# Luxeon_Rebel_Controller_Board.net
KiCad netlist of a schematic drawn in EAGLE
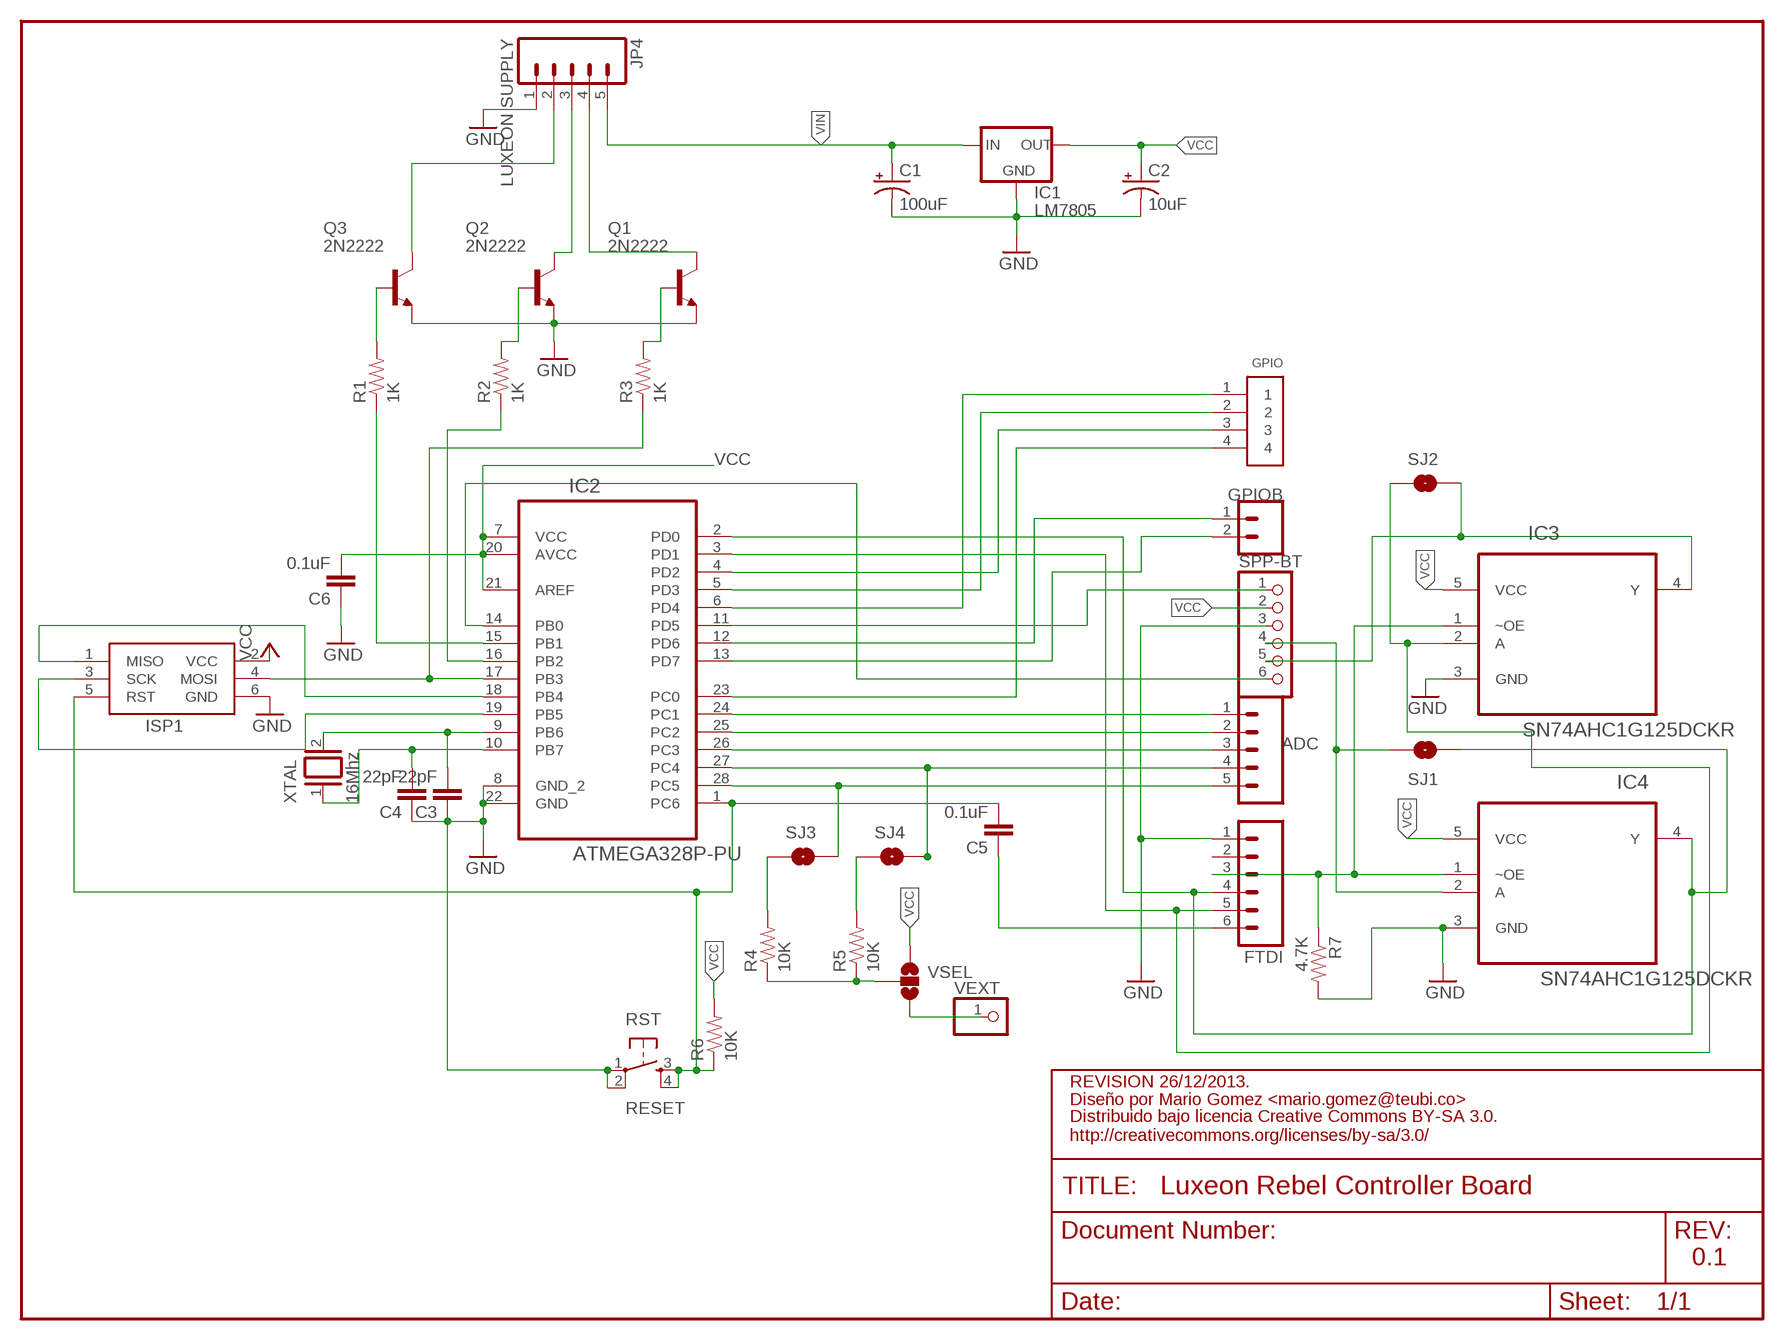
[diagram p0: schematic, sheet 1]

(export (version "E")
  (design (tool "Eeschema 10.0.6"))
  (components
    (comp (ref "ADC")
      (value "M05PTH")
      (footprint "eagle-import:1X05")
      (libsource (lib "eagle-import") (part "SparkFun-Connectors_M05PTH"))
    )
    (comp (ref "C1")
      (value "100uF")
      (footprint "eagle-import:CPOL-RADIAL-100UF-25V")
      (libsource (lib "eagle-import") (part "CAP_POLPTH1"))
    )
    (comp (ref "C2")
      (value "10uF")
      (footprint "eagle-import:CPOL-RADIAL-10UF-25V")
      (libsource (lib "eagle-import") (part "CAP_POLPTH2"))
    )
    (comp (ref "C3")
      (value "22pF")
      (footprint "eagle-import:CAP-PTH-SMALL")
      (libsource (lib "eagle-import") (part "CAPPTH"))
    )
    (comp (ref "C4")
      (value "22pF")
      (footprint "eagle-import:CAP-PTH-SMALL")
      (libsource (lib "eagle-import") (part "CAPPTH"))
    )
    (comp (ref "C5")
      (value "0.1uF")
      (footprint "eagle-import:CAP-PTH-SMALL")
      (libsource (lib "eagle-import") (part "CAPPTH"))
    )
    (comp (ref "C6")
      (value "0.1uF")
      (footprint "eagle-import:CAP-PTH-SMALL")
      (libsource (lib "eagle-import") (part "CAPPTH"))
    )
    (comp (ref "FTDI")
      (value "M06SIP")
      (footprint "eagle-import:1X06")
      (libsource (lib "eagle-import") (part "M06SIP"))
    )
    (comp (ref "GPIO")
      (value "1X4-BIG")
      (footprint "eagle-import:1X04-BIG")
      (libsource (lib "eagle-import") (part "1X4-BIG"))
    )
    (comp (ref "GPIOB")
      (value "M02PTH")
      (footprint "eagle-import:1X02")
      (libsource (lib "eagle-import") (part "M02PTH"))
    )
    (comp (ref "IC1")
      (value "LM7805")
      (footprint "eagle-import:78XXL")
      (libsource (lib "eagle-import") (part "V_REG_78XXSIDE"))
    )
    (comp (ref "IC2")
      (value "ATMEGA328P-PU")
      (footprint "eagle-import:DIP254P762X457-28")
      (libsource (lib "eagle-import") (part "ATMEGA328P-PU"))
    )
    (comp (ref "IC3")
      (value "SN74AHC1G125DCKR")
      (footprint "eagle-import:SOT65P210X110-5N")
      (libsource (lib "eagle-import") (part "SN74AHC1G125DCKR"))
    )
    (comp (ref "IC4")
      (value "SN74AHC1G125DCKR")
      (footprint "eagle-import:SOT65P210X110-5N")
      (libsource (lib "eagle-import") (part "SN74AHC1G125DCKR"))
    )
    (comp (ref "ISP1")
      (value "AVRISP-6")
      (footprint "eagle-import:AVRISP")
      (libsource (lib "eagle-import") (part "AVRISP-6"))
    )
    (comp (ref "JP4")
      (value "LUXEON SUPPLY")
      (footprint "eagle-import:1X05_LONGPADS")
      (libsource (lib "eagle-import") (part "M05PTH_LONGPADS"))
    )
    (comp (ref "Q1")
      (value "2N2222")
      (footprint "eagle-import:TO92-EBC-OVAL")
      (libsource (lib "eagle-import") (part "2N2222"))
    )
    (comp (ref "Q2")
      (value "2N2222")
      (footprint "eagle-import:TO92-EBC-OVAL")
      (libsource (lib "eagle-import") (part "2N2222"))
    )
    (comp (ref "Q3")
      (value "2N2222")
      (footprint "eagle-import:TO92-EBC-OVAL")
      (libsource (lib "eagle-import") (part "2N2222"))
    )
    (comp (ref "R1")
      (value "1K")
      (footprint "eagle-import:AXIAL-0.3")
      (libsource (lib "eagle-import") (part "RESISTORAXIAL-0.3"))
    )
    (comp (ref "R2")
      (value "1K")
      (footprint "eagle-import:AXIAL-0.3")
      (libsource (lib "eagle-import") (part "RESISTORAXIAL-0.3"))
    )
    (comp (ref "R3")
      (value "1K")
      (footprint "eagle-import:AXIAL-0.3")
      (libsource (lib "eagle-import") (part "RESISTORAXIAL-0.3"))
    )
    (comp (ref "R4")
      (value "10K")
      (footprint "eagle-import:AXIAL-0.3")
      (libsource (lib "eagle-import") (part "RESISTORAXIAL-0.3"))
    )
    (comp (ref "R5")
      (value "10K")
      (footprint "eagle-import:AXIAL-0.3")
      (libsource (lib "eagle-import") (part "RESISTORAXIAL-0.3"))
    )
    (comp (ref "R6")
      (value "10K")
      (footprint "eagle-import:AXIAL-0.3")
      (libsource (lib "eagle-import") (part "RESISTORAXIAL-0.3"))
    )
    (comp (ref "R7")
      (value "4.7K")
      (footprint "eagle-import:0603-RES")
      (libsource (lib "eagle-import") (part "RESISTOR0603-RES"))
    )
    (comp (ref "RST")
      (value "RESET")
      (footprint "eagle-import:TACTILE-PTH")
      (libsource (lib "eagle-import") (part "TAC_SWITCHPTH"))
    )
    (comp (ref "SJ1")
      (value "SOLDERJUMPERNC")
      (footprint "eagle-import:SJ_2S")
      (libsource (lib "eagle-import") (part "SOLDERJUMPERNC"))
    )
    (comp (ref "SJ2")
      (value "SOLDERJUMPERNC")
      (footprint "eagle-import:SJ_2S")
      (libsource (lib "eagle-import") (part "SOLDERJUMPERNC"))
    )
    (comp (ref "SJ3")
      (value "SOLDERJUMPERTRACE")
      (footprint "eagle-import:SJ_2S-TRACE")
      (libsource (lib "eagle-import") (part "SOLDERJUMPERTRACE"))
    )
    (comp (ref "SJ4")
      (value "SOLDERJUMPERTRACE")
      (footprint "eagle-import:SJ_2S-TRACE")
      (libsource (lib "eagle-import") (part "SOLDERJUMPERTRACE"))
    )
    (comp (ref "SPP-BT")
      (value "PINHD-1X6")
      (footprint "eagle-import:1X06")
      (libsource (lib "eagle-import") (part "PINHD-1X6"))
    )
    (comp (ref "VEXT")
      (value "PINHD-1X1")
      (footprint "eagle-import:1X01")
      (libsource (lib "eagle-import") (part "PINHD-1X1"))
    )
    (comp (ref "VSEL")
      (value "SOLDERJUMPER_2WAY-OLDS")
      (footprint "eagle-import:SJ_3")
      (libsource (lib "eagle-import") (part "SOLDERJUMPER_2WAY-OLDS"))
    )
    (comp (ref "XTAL")
      (value "16Mhz")
      (footprint "eagle-import:QS")
      (libsource (lib "eagle-import") (part "XTAL/S"))
    )
  )
  (nets
    (net (code "1") (name "GND") (class "Default")
      (node (ref "C1") (pin "2") (pinfunction "-_2") (pintype "passive"))
      (node (ref "C2") (pin "2") (pinfunction "-_2") (pintype "passive"))
      (node (ref "C3") (pin "1") (pinfunction "1_1") (pintype "passive"))
      (node (ref "C4") (pin "1") (pinfunction "1_1") (pintype "passive"))
      (node (ref "C6") (pin "1") (pinfunction "1_1") (pintype "passive"))
      (node (ref "FTDI") (pin "1") (pinfunction "1_1") (pintype "passive"))
      (node (ref "IC1") (pin "GND") (pinfunction "GND_GND") (pintype "input"))
      (node (ref "IC2") (pin "22") (pinfunction "GND_22") (pintype "passive"))
      (node (ref "IC2") (pin "8") (pinfunction "GND_2_8") (pintype "passive"))
      (node (ref "IC3") (pin "3") (pinfunction "GND_3") (pintype "passive"))
      (node (ref "IC4") (pin "3") (pinfunction "GND_3") (pintype "passive"))
      (node (ref "ISP1") (pin "6") (pinfunction "GND_6") (pintype "power_in"))
      (node (ref "JP4") (pin "1") (pinfunction "1_1") (pintype "passive"))
      (node (ref "Q1") (pin "E") (pinfunction "E_E") (pintype "passive"))
      (node (ref "Q2") (pin "E") (pinfunction "E_E") (pintype "passive"))
      (node (ref "Q3") (pin "E") (pinfunction "E_E") (pintype "passive"))
      (node (ref "R7") (pin "2") (pinfunction "2_2") (pintype "passive"))
      (node (ref "RST") (pin "1") (pinfunction "1_1") (pintype "passive"))
      (node (ref "RST") (pin "2") (pinfunction "2_2") (pintype "passive"))
      (node (ref "SPP-BT") (pin "3") (pinfunction "3_3") (pintype "passive"))
    )
    (net (code "2") (name "Net-(C5-Pad1)") (class "Default")
      (node (ref "C5") (pin "1") (pinfunction "1_1") (pintype "passive"))
      (node (ref "FTDI") (pin "6") (pinfunction "6_6") (pintype "passive"))
    )
    (net (code "3") (name "Net-(IC2-PB0)") (class "Default")
      (node (ref "IC2") (pin "14") (pinfunction "PB0_14") (pintype "bidirectional"))
      (node (ref "SPP-BT") (pin "6") (pinfunction "6_6") (pintype "passive"))
    )
    (net (code "4") (name "Net-(IC2-PB1)") (class "Default")
      (node (ref "IC2") (pin "15") (pinfunction "PB1_15") (pintype "bidirectional"))
      (node (ref "R1") (pin "P$1") (pinfunction "1_P$1") (pintype "passive"))
    )
    (net (code "5") (name "Net-(IC2-PB2)") (class "Default")
      (node (ref "IC2") (pin "16") (pinfunction "PB2_16") (pintype "bidirectional"))
      (node (ref "R2") (pin "P$1") (pinfunction "1_P$1") (pintype "passive"))
    )
    (net (code "6") (name "Net-(IC2-PB3)") (class "Default")
      (node (ref "IC2") (pin "17") (pinfunction "PB3_17") (pintype "bidirectional"))
      (node (ref "ISP1") (pin "4") (pinfunction "MOSI_4") (pintype "output"))
      (node (ref "R3") (pin "P$1") (pinfunction "1_P$1") (pintype "passive"))
    )
    (net (code "7") (name "Net-(IC2-PB4)") (class "Default")
      (node (ref "IC2") (pin "18") (pinfunction "PB4_18") (pintype "bidirectional"))
      (node (ref "ISP1") (pin "1") (pinfunction "MISO_1") (pintype "input"))
    )
    (net (code "8") (name "Net-(IC2-PB5)") (class "Default")
      (node (ref "IC2") (pin "19") (pinfunction "PB5_19") (pintype "bidirectional"))
      (node (ref "ISP1") (pin "3") (pinfunction "SCK_3") (pintype "output"))
    )
    (net (code "9") (name "Net-(IC2-PB6)") (class "Default")
      (node (ref "C3") (pin "2") (pinfunction "2_2") (pintype "passive"))
      (node (ref "IC2") (pin "9") (pinfunction "PB6_9") (pintype "bidirectional"))
      (node (ref "XTAL") (pin "2") (pinfunction "2_2") (pintype "passive"))
    )
    (net (code "10") (name "Net-(IC2-PB7)") (class "Default")
      (node (ref "C4") (pin "2") (pinfunction "2_2") (pintype "passive"))
      (node (ref "IC2") (pin "10") (pinfunction "PB7_10") (pintype "bidirectional"))
      (node (ref "XTAL") (pin "1") (pinfunction "1_1") (pintype "passive"))
    )
    (net (code "11") (name "Net-(IC2-PC0)") (class "Default")
      (node (ref "GPIO") (pin "4") (pinfunction "4_4") (pintype "bidirectional"))
      (node (ref "IC2") (pin "23") (pinfunction "PC0_23") (pintype "bidirectional"))
    )
    (net (code "12") (name "Net-(IC2-PC1)") (class "Default")
      (node (ref "ADC") (pin "1") (pinfunction "1_1") (pintype "passive"))
      (node (ref "IC2") (pin "24") (pinfunction "PC1_24") (pintype "bidirectional"))
    )
    (net (code "13") (name "Net-(IC2-PC2)") (class "Default")
      (node (ref "ADC") (pin "2") (pinfunction "2_2") (pintype "passive"))
      (node (ref "IC2") (pin "25") (pinfunction "PC2_25") (pintype "bidirectional"))
    )
    (net (code "14") (name "Net-(IC2-PC3)") (class "Default")
      (node (ref "ADC") (pin "3") (pinfunction "3_3") (pintype "passive"))
      (node (ref "IC2") (pin "26") (pinfunction "PC3_26") (pintype "bidirectional"))
    )
    (net (code "15") (name "Net-(IC2-PC4)") (class "Default")
      (node (ref "ADC") (pin "4") (pinfunction "4_4") (pintype "passive"))
      (node (ref "IC2") (pin "27") (pinfunction "PC4_27") (pintype "bidirectional"))
      (node (ref "SJ4") (pin "2") (pinfunction "2_2") (pintype "passive"))
    )
    (net (code "16") (name "Net-(IC2-PC5)") (class "Default")
      (node (ref "ADC") (pin "5") (pinfunction "5_5") (pintype "passive"))
      (node (ref "IC2") (pin "28") (pinfunction "PC5_28") (pintype "bidirectional"))
      (node (ref "SJ3") (pin "2") (pinfunction "2_2") (pintype "passive"))
    )
    (net (code "17") (name "Net-(IC2-PC6)") (class "Default")
      (node (ref "C5") (pin "2") (pinfunction "2_2") (pintype "passive"))
      (node (ref "IC2") (pin "1") (pinfunction "PC6_1") (pintype "bidirectional"))
      (node (ref "ISP1") (pin "5") (pinfunction "RST_5") (pintype "output"))
      (node (ref "R6") (pin "P$1") (pinfunction "1_P$1") (pintype "passive"))
      (node (ref "RST") (pin "3") (pinfunction "3_3") (pintype "passive"))
      (node (ref "RST") (pin "4") (pinfunction "4_4") (pintype "passive"))
    )
    (net (code "18") (name "Net-(IC2-PD0)") (class "Default")
      (node (ref "FTDI") (pin "4") (pinfunction "4_4") (pintype "passive"))
      (node (ref "IC2") (pin "2") (pinfunction "PD0_2") (pintype "bidirectional"))
      (node (ref "IC4") (pin "4") (pinfunction "Y_4") (pintype "output"))
      (node (ref "SJ1") (pin "2") (pinfunction "2_2") (pintype "passive"))
    )
    (net (code "19") (name "Net-(IC2-PD1)") (class "Default")
      (node (ref "FTDI") (pin "5") (pinfunction "5_5") (pintype "passive"))
      (node (ref "IC2") (pin "3") (pinfunction "PD1_3") (pintype "bidirectional"))
      (node (ref "IC3") (pin "2") (pinfunction "A_2") (pintype "input"))
      (node (ref "SJ2") (pin "1") (pinfunction "1_1") (pintype "passive"))
    )
    (net (code "20") (name "Net-(IC2-PD2)") (class "Default")
      (node (ref "GPIO") (pin "3") (pinfunction "3_3") (pintype "bidirectional"))
      (node (ref "IC2") (pin "4") (pinfunction "PD2_4") (pintype "bidirectional"))
    )
    (net (code "21") (name "Net-(IC2-PD3)") (class "Default")
      (node (ref "GPIO") (pin "2") (pinfunction "2_2") (pintype "bidirectional"))
      (node (ref "IC2") (pin "5") (pinfunction "PD3_5") (pintype "bidirectional"))
    )
    (net (code "22") (name "Net-(IC2-PD4)") (class "Default")
      (node (ref "GPIO") (pin "1") (pinfunction "1_1") (pintype "bidirectional"))
      (node (ref "IC2") (pin "6") (pinfunction "PD4_6") (pintype "bidirectional"))
    )
    (net (code "23") (name "Net-(IC2-PD5)") (class "Default")
      (node (ref "IC2") (pin "11") (pinfunction "PD5_11") (pintype "bidirectional"))
      (node (ref "SPP-BT") (pin "1") (pinfunction "1_1") (pintype "passive"))
    )
    (net (code "24") (name "Net-(IC2-PD6)") (class "Default")
      (node (ref "GPIOB") (pin "1") (pinfunction "1_1") (pintype "passive"))
      (node (ref "IC2") (pin "12") (pinfunction "PD6_12") (pintype "bidirectional"))
    )
    (net (code "25") (name "Net-(IC2-PD7)") (class "Default")
      (node (ref "GPIOB") (pin "2") (pinfunction "2_2") (pintype "passive"))
      (node (ref "IC2") (pin "13") (pinfunction "PD7_13") (pintype "bidirectional"))
    )
    (net (code "26") (name "Net-(IC3-Y)") (class "Default")
      (node (ref "IC3") (pin "4") (pinfunction "Y_4") (pintype "output"))
      (node (ref "SJ2") (pin "2") (pinfunction "2_2") (pintype "passive"))
      (node (ref "SPP-BT") (pin "5") (pinfunction "5_5") (pintype "passive"))
    )
    (net (code "27") (name "Net-(IC3-~{OE})") (class "Default")
      (node (ref "FTDI") (pin "3") (pinfunction "3_3") (pintype "passive"))
      (node (ref "IC3") (pin "1") (pinfunction "~{OE}_1") (pintype "input"))
      (node (ref "IC4") (pin "1") (pinfunction "~{OE}_1") (pintype "input"))
      (node (ref "R7") (pin "1") (pinfunction "1_1") (pintype "passive"))
    )
    (net (code "28") (name "Net-(IC4-A)") (class "Default")
      (node (ref "IC4") (pin "2") (pinfunction "A_2") (pintype "input"))
      (node (ref "SJ1") (pin "1") (pinfunction "1_1") (pintype "passive"))
      (node (ref "SPP-BT") (pin "4") (pinfunction "4_4") (pintype "passive"))
    )
    (net (code "29") (name "Net-(JP4-Pad2)") (class "Default")
      (node (ref "JP4") (pin "2") (pinfunction "2_2") (pintype "passive"))
      (node (ref "Q3") (pin "C") (pinfunction "C_C") (pintype "passive"))
    )
    (net (code "30") (name "Net-(JP4-Pad3)") (class "Default")
      (node (ref "JP4") (pin "3") (pinfunction "3_3") (pintype "passive"))
      (node (ref "Q2") (pin "C") (pinfunction "C_C") (pintype "passive"))
    )
    (net (code "31") (name "Net-(JP4-Pad4)") (class "Default")
      (node (ref "JP4") (pin "4") (pinfunction "4_4") (pintype "passive"))
      (node (ref "Q1") (pin "C") (pinfunction "C_C") (pintype "passive"))
    )
    (net (code "32") (name "Net-(R1-2)") (class "Default")
      (node (ref "Q3") (pin "B") (pinfunction "B_B") (pintype "passive"))
      (node (ref "R1") (pin "P$2") (pinfunction "2_P$2") (pintype "passive"))
    )
    (net (code "33") (name "Net-(R2-2)") (class "Default")
      (node (ref "Q2") (pin "B") (pinfunction "B_B") (pintype "passive"))
      (node (ref "R2") (pin "P$2") (pinfunction "2_P$2") (pintype "passive"))
    )
    (net (code "34") (name "Net-(R3-2)") (class "Default")
      (node (ref "Q1") (pin "B") (pinfunction "B_B") (pintype "passive"))
      (node (ref "R3") (pin "P$2") (pinfunction "2_P$2") (pintype "passive"))
    )
    (net (code "35") (name "Net-(R4-1)") (class "Default")
      (node (ref "R4") (pin "P$1") (pinfunction "1_P$1") (pintype "passive"))
      (node (ref "R5") (pin "P$1") (pinfunction "1_P$1") (pintype "passive"))
      (node (ref "VSEL") (pin "2") (pinfunction "2_2") (pintype "passive"))
    )
    (net (code "36") (name "Net-(R4-2)") (class "Default")
      (node (ref "R4") (pin "P$2") (pinfunction "2_P$2") (pintype "passive"))
      (node (ref "SJ3") (pin "1") (pinfunction "1_1") (pintype "passive"))
    )
    (net (code "37") (name "Net-(R5-2)") (class "Default")
      (node (ref "R5") (pin "P$2") (pinfunction "2_P$2") (pintype "passive"))
      (node (ref "SJ4") (pin "1") (pinfunction "1_1") (pintype "passive"))
    )
    (net (code "38") (name "Net-(VEXT-Pad1)") (class "Default")
      (node (ref "VEXT") (pin "1") (pinfunction "1_1") (pintype "passive"))
      (node (ref "VSEL") (pin "3") (pinfunction "3_3") (pintype "passive"))
    )
    (net (code "39") (name "VCC") (class "Default")
      (node (ref "C2") (pin "1") (pinfunction "+_1") (pintype "passive"))
      (node (ref "C6") (pin "2") (pinfunction "2_2") (pintype "passive"))
      (node (ref "IC1") (pin "OUT") (pinfunction "OUT_OUT") (pintype "output"))
      (node (ref "IC2") (pin "20") (pinfunction "AVCC_20") (pintype "power_in"))
      (node (ref "IC2") (pin "21") (pinfunction "AREF_21") (pintype "input"))
      (node (ref "IC2") (pin "7") (pinfunction "VCC_7") (pintype "power_in"))
      (node (ref "IC3") (pin "5") (pinfunction "VCC_5") (pintype "power_in"))
      (node (ref "IC4") (pin "5") (pinfunction "VCC_5") (pintype "power_in"))
      (node (ref "ISP1") (pin "2") (pinfunction "VCC_2") (pintype "power_in"))
      (node (ref "R6") (pin "P$2") (pinfunction "2_P$2") (pintype "passive"))
      (node (ref "SPP-BT") (pin "2") (pinfunction "2_2") (pintype "passive"))
      (node (ref "VSEL") (pin "1") (pinfunction "1_1") (pintype "passive"))
    )
    (net (code "40") (name "VIN") (class "Default")
      (node (ref "C1") (pin "1") (pinfunction "+_1") (pintype "passive"))
      (node (ref "IC1") (pin "IN") (pinfunction "IN_IN") (pintype "input"))
      (node (ref "JP4") (pin "5") (pinfunction "5_5") (pintype "passive"))
    )
    (net (code "41") (name "unconnected-(FTDI-Pad2)") (class "Default")
      (node (ref "FTDI") (pin "2") (pinfunction "2_2") (pintype "passive"))
    )
  )
)
